# SecondaryMCU.net
KiCad netlist of a schematic drawn in Altium Designer
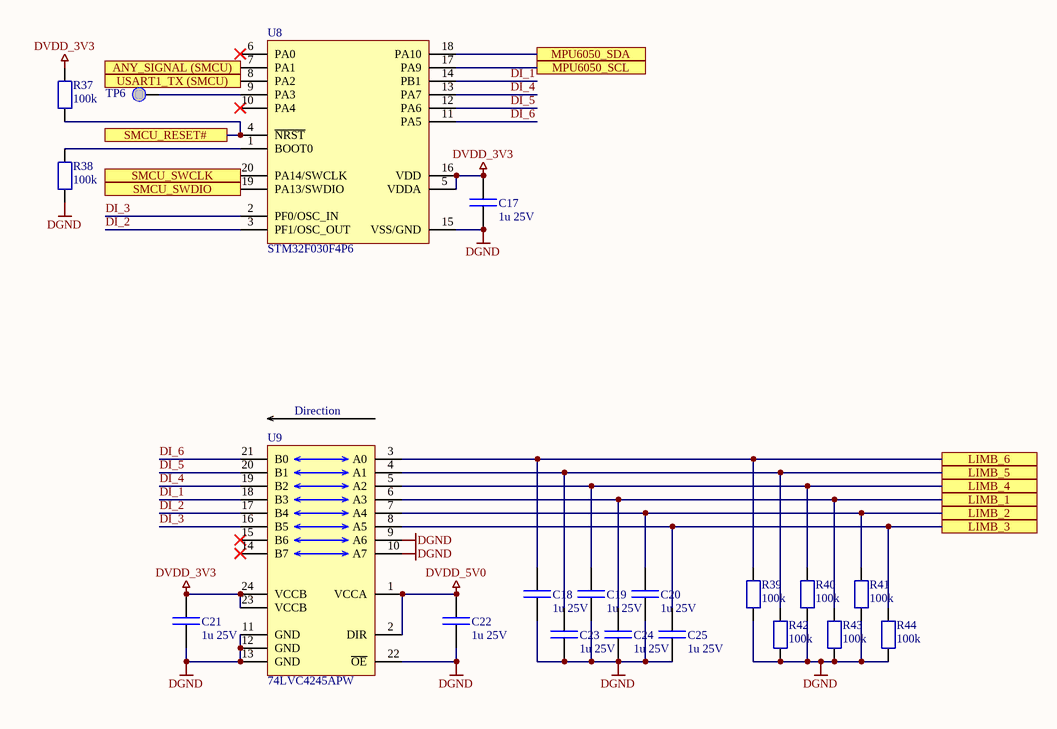
[diagram p0: SecondaryMCU.SchDoc]

(export (version "E")
  (design (tool "Eeschema 10.0.6"))
  (components
    (comp (ref "C17")
      (value "1u 25V")
      (footprint "C_0603/1608")
      (description "Non-polarized capacitor")
      (libsource (lib "passive") (part "Capacitor"))
    )
    (comp (ref "C18")
      (value "1u 25V")
      (footprint "C_0805/2012")
      (description "Non-polarized capacitor")
      (libsource (lib "passive") (part "Capacitor"))
    )
    (comp (ref "C19")
      (value "1u 25V")
      (footprint "C_0805/2012")
      (description "Non-polarized capacitor")
      (libsource (lib "passive") (part "Capacitor"))
    )
    (comp (ref "C20")
      (value "1u 25V")
      (footprint "C_0805/2012")
      (description "Non-polarized capacitor")
      (libsource (lib "passive") (part "Capacitor"))
    )
    (comp (ref "C21")
      (value "1u 25V")
      (footprint "C_0603/1608")
      (description "Non-polarized capacitor")
      (libsource (lib "passive") (part "Capacitor"))
    )
    (comp (ref "C22")
      (value "1u 25V")
      (footprint "C_0603/1608")
      (description "Non-polarized capacitor")
      (libsource (lib "passive") (part "Capacitor"))
    )
    (comp (ref "C23")
      (value "1u 25V")
      (footprint "C_0805/2012")
      (description "Non-polarized capacitor")
      (libsource (lib "passive") (part "Capacitor"))
    )
    (comp (ref "C24")
      (value "1u 25V")
      (footprint "C_0805/2012")
      (description "Non-polarized capacitor")
      (libsource (lib "passive") (part "Capacitor"))
    )
    (comp (ref "C25")
      (value "1u 25V")
      (footprint "C_0805/2012")
      (description "Non-polarized capacitor")
      (libsource (lib "passive") (part "Capacitor"))
    )
    (comp (ref "R37")
      (value "100k")
      (footprint "R_0603/1608")
      (description "Resistor")
      (libsource (lib "passive") (part "Resistor"))
    )
    (comp (ref "R38")
      (value "100k")
      (footprint "R_0603/1608")
      (description "Resistor")
      (libsource (lib "passive") (part "Resistor"))
    )
    (comp (ref "R39")
      (value "100k")
      (footprint "R_0402/1005")
      (description "Resistor")
      (libsource (lib "passive") (part "Resistor"))
    )
    (comp (ref "R40")
      (value "100k")
      (footprint "R_0402/1005")
      (description "Resistor")
      (libsource (lib "passive") (part "Resistor"))
    )
    (comp (ref "R41")
      (value "100k")
      (footprint "R_0402/1005")
      (description "Resistor")
      (libsource (lib "passive") (part "Resistor"))
    )
    (comp (ref "R42")
      (value "100k")
      (footprint "R_0402/1005")
      (description "Resistor")
      (libsource (lib "passive") (part "Resistor"))
    )
    (comp (ref "R43")
      (value "100k")
      (footprint "R_0402/1005")
      (description "Resistor")
      (libsource (lib "passive") (part "Resistor"))
    )
    (comp (ref "R44")
      (value "100k")
      (footprint "R_0402/1005")
      (description "Resistor")
      (libsource (lib "passive") (part "Resistor"))
    )
    (comp (ref "TP6")
      (value "Debug")
      (footprint "TP_SMD_D1.00")
      (description "Test point")
      (libsource (lib "connectors") (part "Test point"))
    )
    (comp (ref "U8")
      (value "STM32F030F4P6")
      (footprint "SO20_0.65")
      (description "32-bit Cortex-M0")
      (libsource (lib "MCU and memory") (part "STM32F030F"))
    )
    (comp (ref "U9")
      (value "74LVC4245APW")
      (footprint "SO24_0.65")
      (description "Logic level converter")
      (libsource (lib "digital") (part "74LVC4245APW"))
    )
  )
  (nets
    (net (code "1") (name "/ANY_SIGNAL (SMCU)") (class "Default")
      (node (ref "U8") (pin "7") (pinfunction "PA1_7") (pintype "passive"))
    )
    (net (code "2") (name "/DI_1") (class "Default")
      (node (ref "U8") (pin "14") (pinfunction "PB1_14") (pintype "passive"))
      (node (ref "U9") (pin "18") (pinfunction "B3_18") (pintype "passive"))
    )
    (net (code "3") (name "/DI_2") (class "Default")
      (node (ref "U8") (pin "3") (pinfunction "PF1/OSC_OUT_3") (pintype "passive"))
      (node (ref "U9") (pin "17") (pinfunction "B4_17") (pintype "passive"))
    )
    (net (code "4") (name "/DI_3") (class "Default")
      (node (ref "U8") (pin "2") (pinfunction "PF0/OSC_IN_2") (pintype "passive"))
      (node (ref "U9") (pin "16") (pinfunction "B5_16") (pintype "passive"))
    )
    (net (code "5") (name "/DI_4") (class "Default")
      (node (ref "U8") (pin "13") (pinfunction "PA7_13") (pintype "passive"))
      (node (ref "U9") (pin "19") (pinfunction "B2_19") (pintype "passive"))
    )
    (net (code "6") (name "/DI_5") (class "Default")
      (node (ref "U8") (pin "12") (pinfunction "PA6_12") (pintype "passive"))
      (node (ref "U9") (pin "20") (pinfunction "B1_20") (pintype "passive"))
    )
    (net (code "7") (name "/DI_6") (class "Default")
      (node (ref "U8") (pin "11") (pinfunction "PA5_11") (pintype "passive"))
      (node (ref "U9") (pin "21") (pinfunction "B0_21") (pintype "passive"))
    )
    (net (code "8") (name "/LIMB_1") (class "Default")
      (node (ref "C24") (pin "1") (pintype "passive"))
      (node (ref "R43") (pin "1") (pintype "passive"))
      (node (ref "U9") (pin "6") (pinfunction "A3_6") (pintype "passive"))
    )
    (net (code "9") (name "/LIMB_2") (class "Default")
      (node (ref "C20") (pin "1") (pintype "passive"))
      (node (ref "R41") (pin "1") (pintype "passive"))
      (node (ref "U9") (pin "7") (pinfunction "A4_7") (pintype "passive"))
    )
    (net (code "10") (name "/LIMB_3") (class "Default")
      (node (ref "C25") (pin "1") (pintype "passive"))
      (node (ref "R44") (pin "1") (pintype "passive"))
      (node (ref "U9") (pin "8") (pinfunction "A5_8") (pintype "passive"))
    )
    (net (code "11") (name "/LIMB_4") (class "Default")
      (node (ref "C19") (pin "1") (pintype "passive"))
      (node (ref "R40") (pin "1") (pintype "passive"))
      (node (ref "U9") (pin "5") (pinfunction "A2_5") (pintype "passive"))
    )
    (net (code "12") (name "/LIMB_5") (class "Default")
      (node (ref "C23") (pin "1") (pintype "passive"))
      (node (ref "R42") (pin "1") (pintype "passive"))
      (node (ref "U9") (pin "4") (pinfunction "A1_4") (pintype "passive"))
    )
    (net (code "13") (name "/LIMB_6") (class "Default")
      (node (ref "C18") (pin "1") (pintype "passive"))
      (node (ref "R39") (pin "1") (pintype "passive"))
      (node (ref "U9") (pin "3") (pinfunction "A0_3") (pintype "passive"))
    )
    (net (code "14") (name "/MPU6050_SCL") (class "Default")
      (node (ref "U8") (pin "17") (pinfunction "PA9_17") (pintype "passive"))
    )
    (net (code "15") (name "/MPU6050_SDA") (class "Default")
      (node (ref "U8") (pin "18") (pinfunction "PA10_18") (pintype "passive"))
    )
    (net (code "16") (name "/SMCU_RESET#") (class "Default")
      (node (ref "R37") (pin "2") (pintype "passive"))
      (node (ref "U8") (pin "4") (pinfunction "~{NRST}_4") (pintype "passive"))
    )
    (net (code "17") (name "/SMCU_SWCLK") (class "Default")
      (node (ref "U8") (pin "20") (pinfunction "PA14/SWCLK_20") (pintype "passive"))
    )
    (net (code "18") (name "/SMCU_SWDIO") (class "Default")
      (node (ref "U8") (pin "19") (pinfunction "PA13/SWDIO_19") (pintype "passive"))
    )
    (net (code "19") (name "/USART1_TX (SMCU)") (class "Default")
      (node (ref "U8") (pin "8") (pinfunction "PA2_8") (pintype "passive"))
    )
    (net (code "20") (name "DGND") (class "Default")
      (node (ref "C17") (pin "2") (pintype "passive"))
      (node (ref "C18") (pin "2") (pintype "passive"))
      (node (ref "C19") (pin "2") (pintype "passive"))
      (node (ref "C20") (pin "2") (pintype "passive"))
      (node (ref "C21") (pin "2") (pintype "passive"))
      (node (ref "C22") (pin "2") (pintype "passive"))
      (node (ref "C23") (pin "2") (pintype "passive"))
      (node (ref "C24") (pin "2") (pintype "passive"))
      (node (ref "C25") (pin "2") (pintype "passive"))
      (node (ref "R38") (pin "2") (pintype "passive"))
      (node (ref "R39") (pin "2") (pintype "passive"))
      (node (ref "R40") (pin "2") (pintype "passive"))
      (node (ref "R41") (pin "2") (pintype "passive"))
      (node (ref "R42") (pin "2") (pintype "passive"))
      (node (ref "R43") (pin "2") (pintype "passive"))
      (node (ref "R44") (pin "2") (pintype "passive"))
      (node (ref "U8") (pin "15") (pinfunction "VSS/GND_15") (pintype "passive"))
      (node (ref "U9") (pin "10") (pinfunction "A7_10") (pintype "passive"))
      (node (ref "U9") (pin "11") (pinfunction "GND_11") (pintype "passive"))
      (node (ref "U9") (pin "12") (pinfunction "GND_12") (pintype "passive"))
      (node (ref "U9") (pin "13") (pinfunction "GND_13") (pintype "passive"))
      (node (ref "U9") (pin "22") (pinfunction "~{OE}_22") (pintype "passive"))
      (node (ref "U9") (pin "9") (pinfunction "A6_9") (pintype "passive"))
    )
    (net (code "21") (name "DVDD_3V3") (class "Default")
      (node (ref "C17") (pin "1") (pintype "passive"))
      (node (ref "C21") (pin "1") (pintype "passive"))
      (node (ref "R37") (pin "1") (pintype "passive"))
      (node (ref "U8") (pin "16") (pinfunction "VDD_16") (pintype "passive"))
      (node (ref "U8") (pin "5") (pinfunction "VDDA_5") (pintype "passive"))
      (node (ref "U9") (pin "23") (pinfunction "VCCB_23") (pintype "passive"))
      (node (ref "U9") (pin "24") (pinfunction "VCCB_24") (pintype "passive"))
    )
    (net (code "22") (name "DVDD_5V0") (class "Default")
      (node (ref "C22") (pin "1") (pintype "passive"))
      (node (ref "U9") (pin "1") (pinfunction "VCCA_1") (pintype "passive"))
      (node (ref "U9") (pin "2") (pinfunction "DIR_2") (pintype "passive"))
    )
    (net (code "23") (name "Net-(U8-BOOT0)") (class "Default")
      (node (ref "R38") (pin "1") (pintype "passive"))
      (node (ref "U8") (pin "1") (pinfunction "BOOT0_1") (pintype "passive"))
    )
    (net (code "24") (name "Net-(U8-PA3)") (class "Default")
      (node (ref "TP6") (pin "1") (pintype "passive"))
      (node (ref "U8") (pin "9") (pinfunction "PA3_9") (pintype "passive"))
    )
    (net (code "25") (name "unconnected-(U8-EP-Pad0)") (class "Default")
      (node (ref "U8") (pin "0") (pinfunction "EP_0") (pintype "passive"))
    )
    (net (code "26") (name "unconnected-(U8-PA0-Pad6)") (class "Default")
      (node (ref "U8") (pin "6") (pinfunction "PA0_6") (pintype "passive+no_connect"))
    )
    (net (code "27") (name "unconnected-(U8-PA4-Pad10)") (class "Default")
      (node (ref "U8") (pin "10") (pinfunction "PA4_10") (pintype "passive+no_connect"))
    )
    (net (code "28") (name "unconnected-(U9-B6-Pad15)") (class "Default")
      (node (ref "U9") (pin "15") (pinfunction "B6_15") (pintype "passive+no_connect"))
    )
    (net (code "29") (name "unconnected-(U9-B7-Pad14)") (class "Default")
      (node (ref "U9") (pin "14") (pinfunction "B7_14") (pintype "passive+no_connect"))
    )
  )
)
